# Schematic.net
KiCad netlist of a schematic drawn in EAGLE
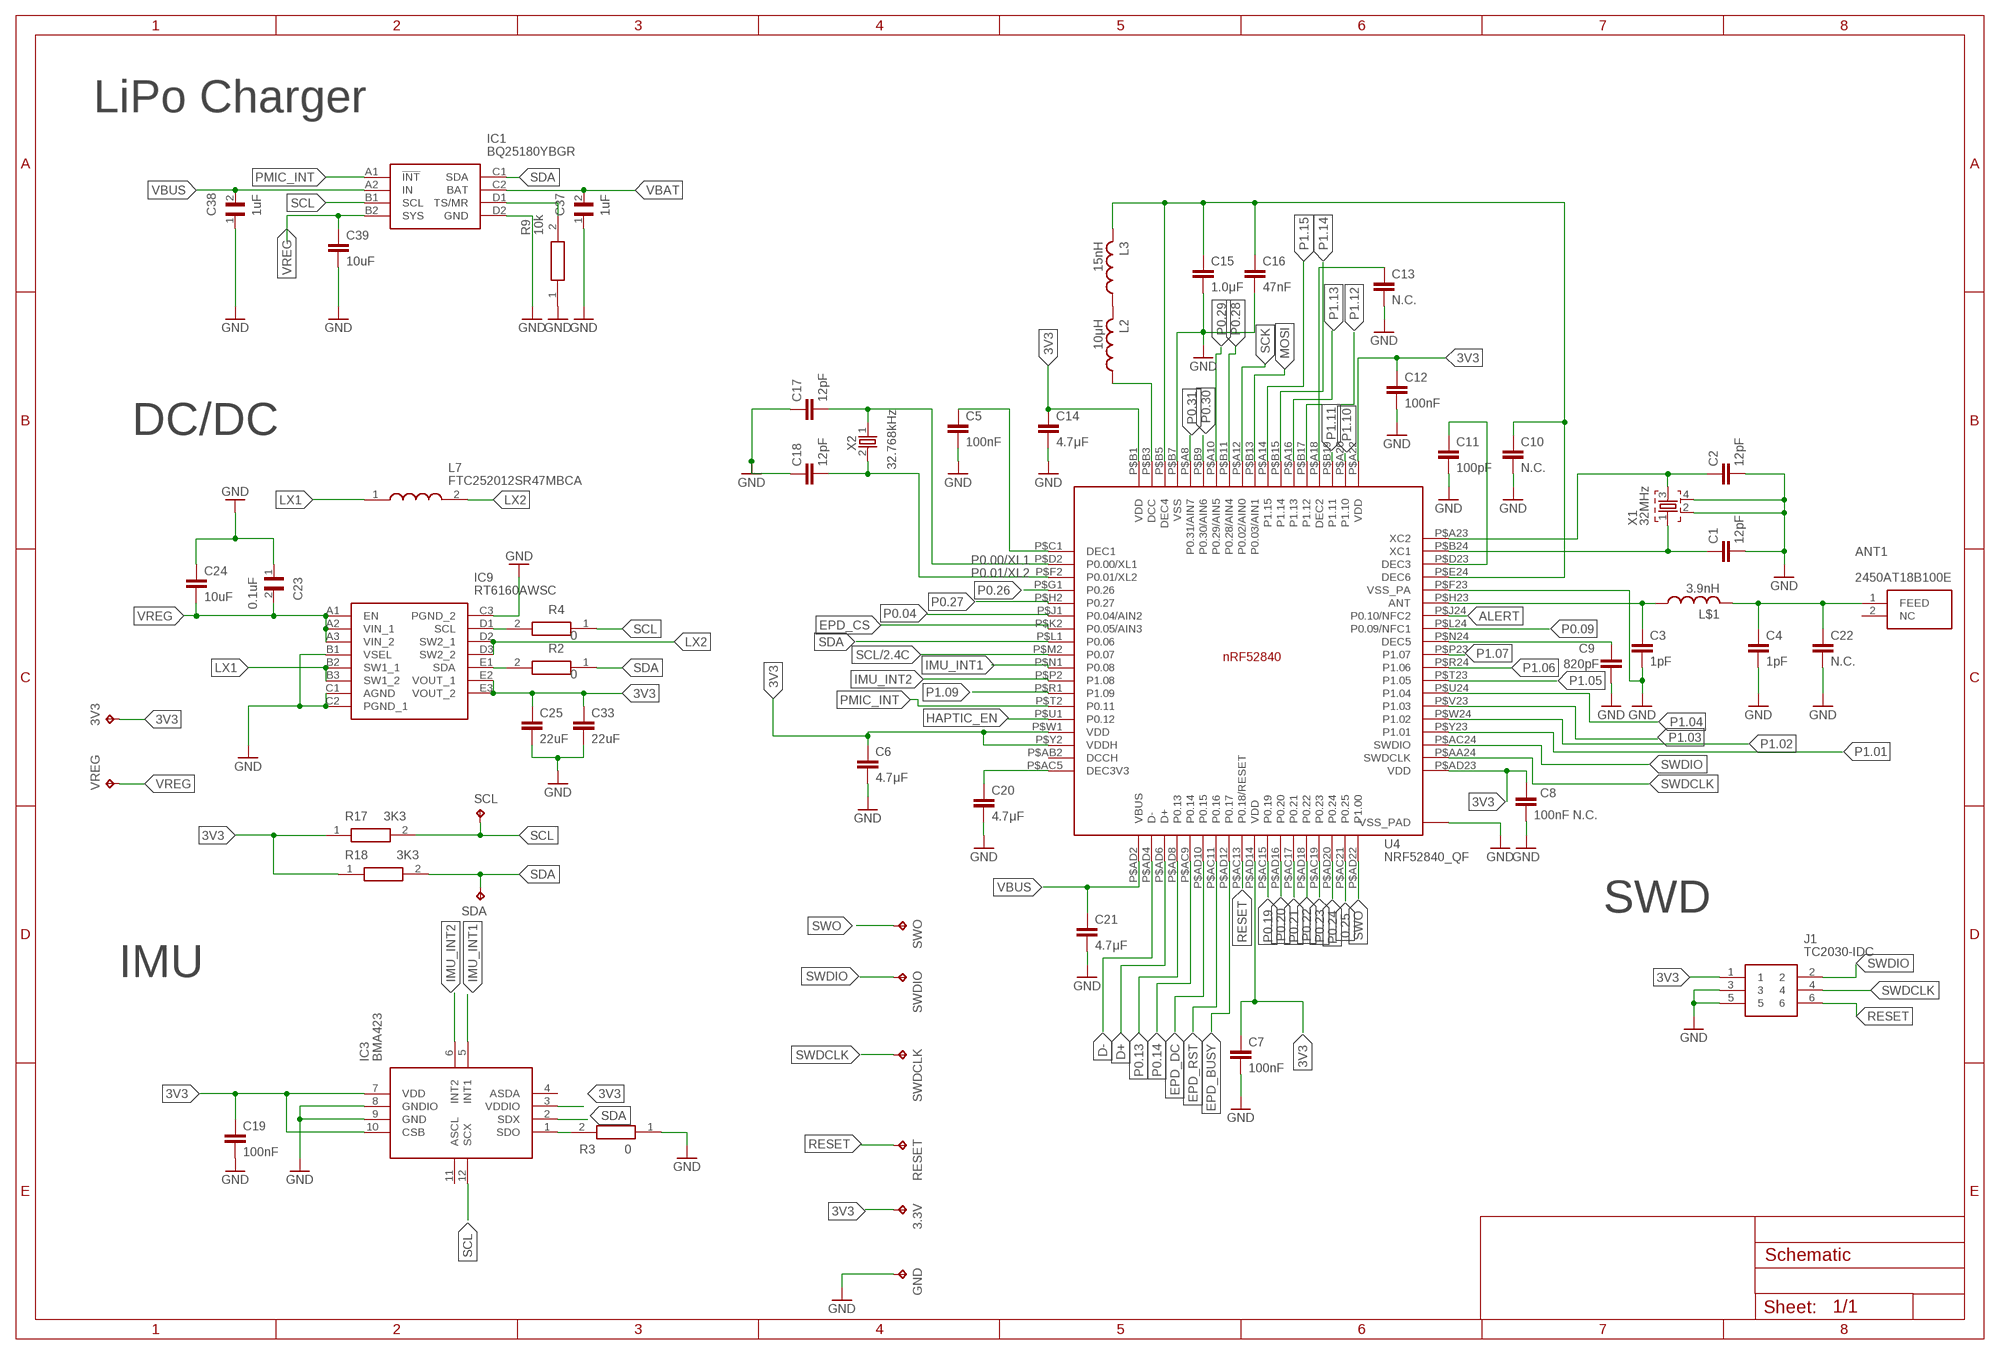
[diagram p0: schematic, sheet 1, part 1 of 2]
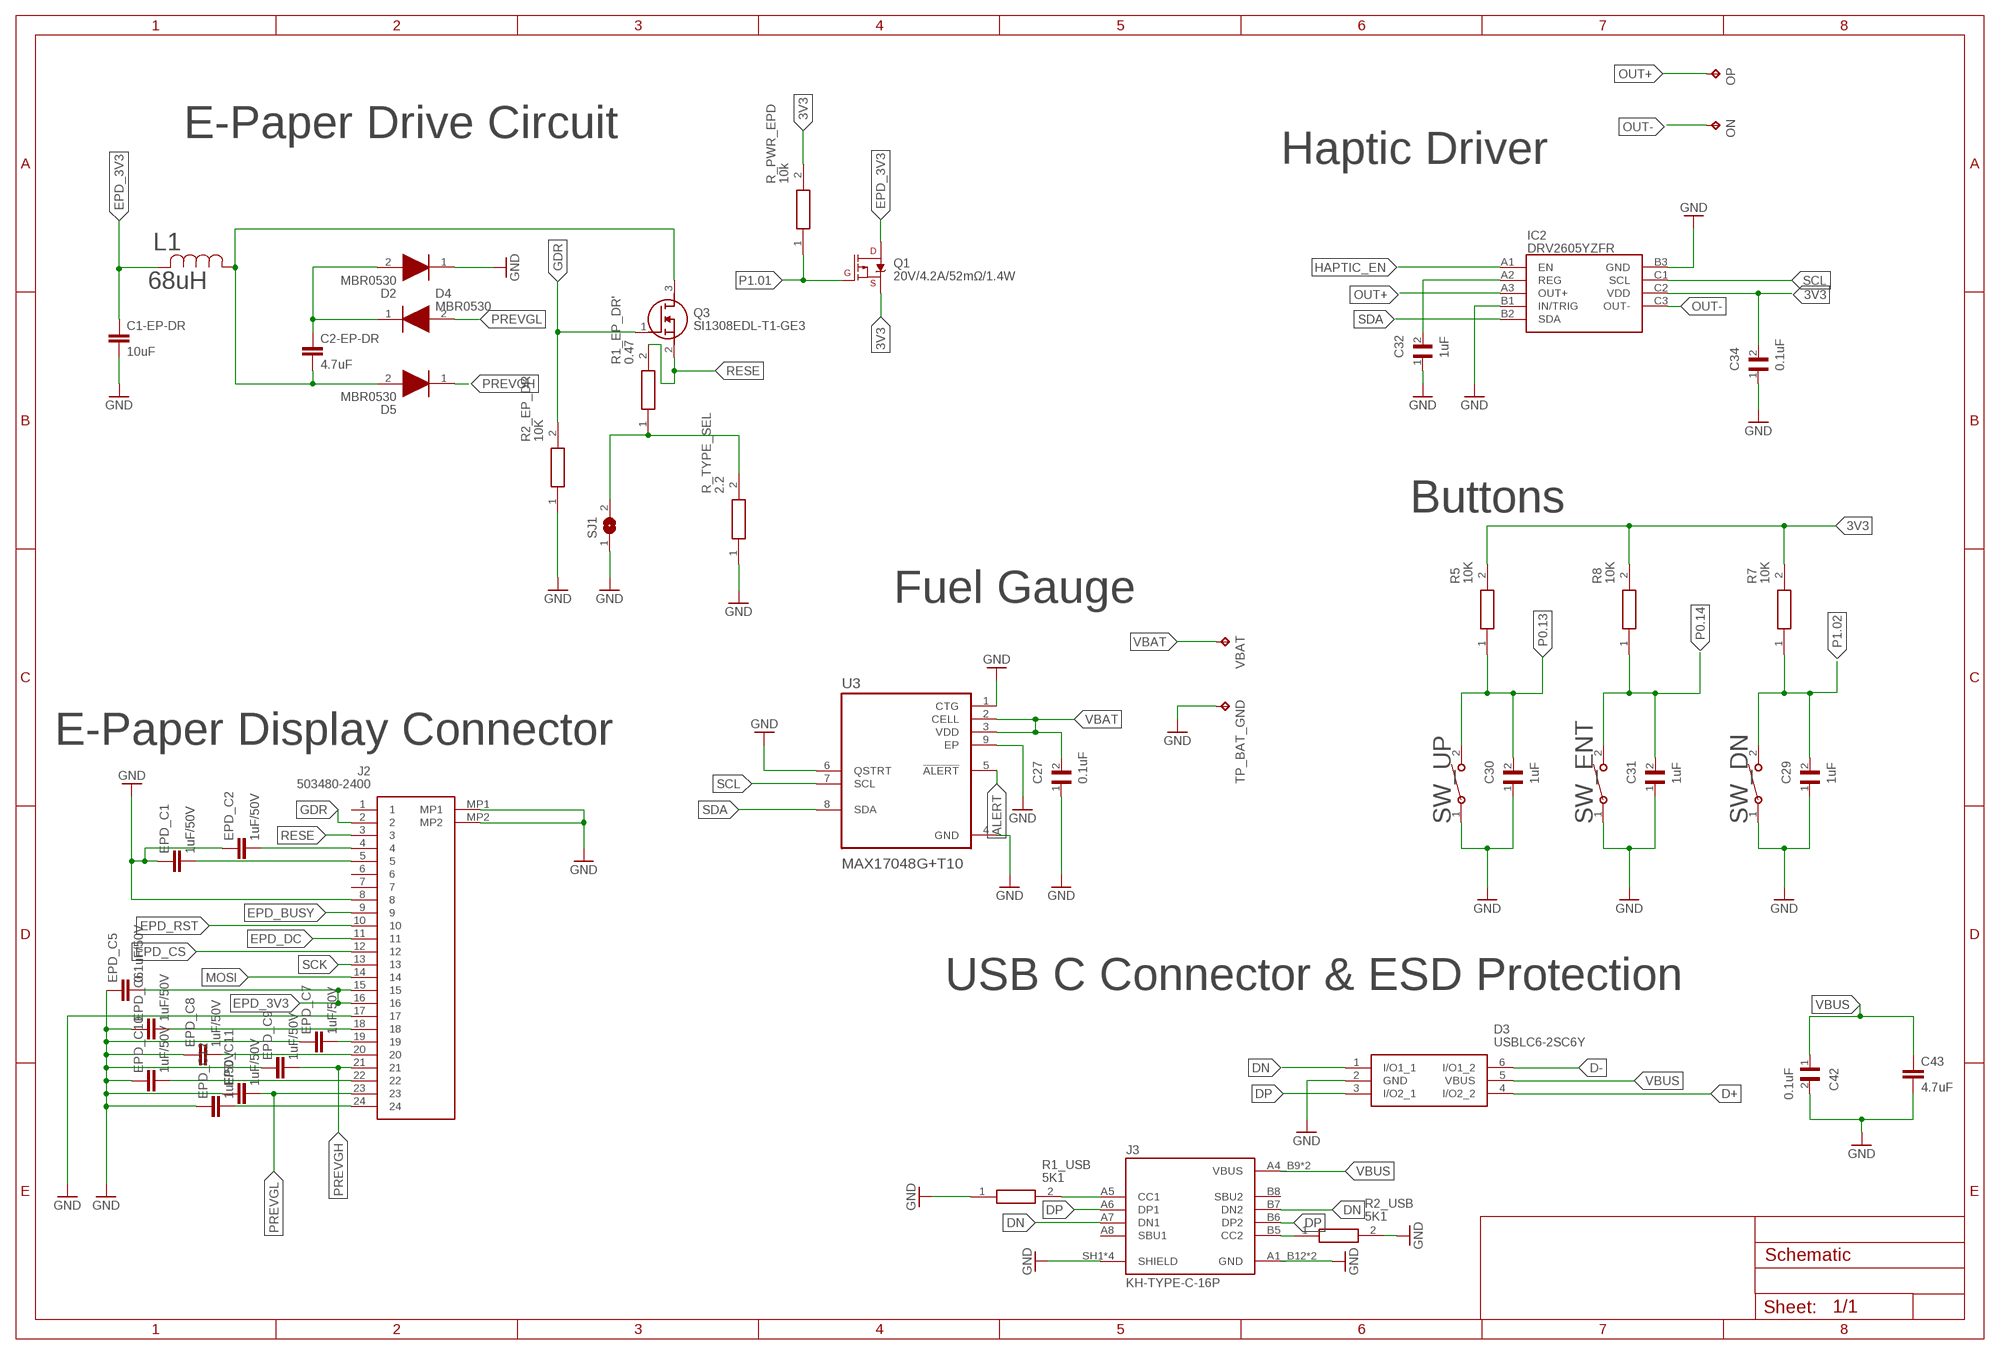
[diagram p1: schematic, sheet 1, part 2 of 2]

(export (version "E")
  (design (tool "Eeschema 10.0.6"))
  (components
    (comp (ref "3.3V")
      (value "HECTOR_WATCH_1_TPTP20R")
      (footprint "eagle-import:HECTOR_WATCH_1_TP20R")
      (libsource (lib "eagle-import") (part "HECTOR_WATCH_1_TPTP20R"))
    )
    (comp (ref "3V3")
      (value "HECTOR_WATCH_1_TPTP20R")
      (footprint "eagle-import:HECTOR_WATCH_1_TP20R")
      (libsource (lib "eagle-import") (part "HECTOR_WATCH_1_TPTP20R"))
    )
    (comp (ref "ANT1")
      (value "2450AT18B100E")
      (footprint "eagle-import:2450AT18B100E_ANTC3216X140N")
      (fields (field (name "MOUSER_PART_NUMBER") "609-2450AT18B100E"))
      (libsource (lib "eagle-import") (part "2450AT18B100E_2450AT18B100E"))
    )
    (comp (ref "C1")
      (value "12pF")
      (footprint "eagle-import:NORDIC_NRF_3_RESC0201_L")
      (libsource (lib "eagle-import") (part "NORDIC_NRF_3_CAPACITOR_0201_L"))
    )
    (comp (ref "C1-EP-DR")
      (value "10uF")
      (footprint "eagle-import:NORDIC_NRF_3_RESC0201_L")
      (libsource (lib "eagle-import") (part "NORDIC_NRF_3_CAPACITOR_0201_L"))
    )
    (comp (ref "C2")
      (value "12pF")
      (footprint "eagle-import:NORDIC_NRF_3_RESC0201_L")
      (libsource (lib "eagle-import") (part "NORDIC_NRF_3_CAPACITOR_0201_L"))
    )
    (comp (ref "C2-EP-DR")
      (value "4.7uF")
      (footprint "eagle-import:NORDIC_NRF_3_RESC0201_L")
      (libsource (lib "eagle-import") (part "NORDIC_NRF_3_CAPACITOR_0201_L"))
    )
    (comp (ref "C3")
      (value "1pF")
      (footprint "eagle-import:NORDIC_NRF_3_RESC0201_L")
      (libsource (lib "eagle-import") (part "NORDIC_NRF_3_CAPACITOR_0201_L"))
    )
    (comp (ref "C4")
      (value "1pF")
      (footprint "eagle-import:NORDIC_NRF_3_RESC0201_L")
      (libsource (lib "eagle-import") (part "NORDIC_NRF_3_CAPACITOR_0201_L"))
    )
    (comp (ref "C5")
      (value "100nF")
      (footprint "eagle-import:NORDIC_NRF_3_RESC0201_L")
      (libsource (lib "eagle-import") (part "NORDIC_NRF_3_CAPACITOR_0201_L"))
    )
    (comp (ref "C6")
      (value "4.7μF")
      (footprint "eagle-import:NORDIC_NRF_3_RESC0201_L")
      (libsource (lib "eagle-import") (part "NORDIC_NRF_3_CAPACITOR_0201_L"))
    )
    (comp (ref "C7")
      (value "100nF")
      (footprint "eagle-import:NORDIC_NRF_3_RESC0201_L")
      (libsource (lib "eagle-import") (part "NORDIC_NRF_3_CAPACITOR_0201_L"))
    )
    (comp (ref "C8")
      (value "100nF N.C.")
      (footprint "eagle-import:NORDIC_NRF_3_RESC0201_L")
      (libsource (lib "eagle-import") (part "NORDIC_NRF_3_CAPACITOR_0201_L"))
    )
    (comp (ref "C9")
      (value "820pF")
      (footprint "eagle-import:NORDIC_NRF_3_RESC0201_L")
      (libsource (lib "eagle-import") (part "NORDIC_NRF_3_CAPACITOR_0201_L"))
    )
    (comp (ref "C10")
      (value "N.C.")
      (footprint "eagle-import:NORDIC_NRF_3_RESC0201_L")
      (libsource (lib "eagle-import") (part "NORDIC_NRF_3_CAPACITOR_0201_L"))
    )
    (comp (ref "C11")
      (value "100pF")
      (footprint "eagle-import:NORDIC_NRF_3_RESC0201_L")
      (libsource (lib "eagle-import") (part "NORDIC_NRF_3_CAPACITOR_0201_L"))
    )
    (comp (ref "C12")
      (value "100nF")
      (footprint "eagle-import:NORDIC_NRF_3_RESC0201_L")
      (libsource (lib "eagle-import") (part "NORDIC_NRF_3_CAPACITOR_0201_L"))
    )
    (comp (ref "C13")
      (value "N.C.")
      (footprint "eagle-import:NORDIC_NRF_3_RESC0201_L")
      (libsource (lib "eagle-import") (part "NORDIC_NRF_3_CAPACITOR_0201_L"))
    )
    (comp (ref "C14")
      (value "4.7μF")
      (footprint "eagle-import:NORDIC_NRF_3_RESC0201_L")
      (libsource (lib "eagle-import") (part "NORDIC_NRF_3_CAPACITOR_0201_L"))
    )
    (comp (ref "C15")
      (value "1.0μF")
      (footprint "eagle-import:NORDIC_NRF_3_RESC0201_L")
      (libsource (lib "eagle-import") (part "NORDIC_NRF_3_CAPACITOR_0201_L"))
    )
    (comp (ref "C16")
      (value "47nF")
      (footprint "eagle-import:NORDIC_NRF_3_RESC0201_L")
      (libsource (lib "eagle-import") (part "NORDIC_NRF_3_CAPACITOR_0201_L"))
    )
    (comp (ref "C17")
      (value "12pF")
      (footprint "eagle-import:NORDIC_NRF_3_RESC0201_L")
      (libsource (lib "eagle-import") (part "NORDIC_NRF_3_CAPACITOR_0201_L"))
    )
    (comp (ref "C18")
      (value "12pF")
      (footprint "eagle-import:NORDIC_NRF_3_RESC0201_L")
      (libsource (lib "eagle-import") (part "NORDIC_NRF_3_CAPACITOR_0201_L"))
    )
    (comp (ref "C19")
      (value "100nF")
      (footprint "eagle-import:NORDIC_NRF_3_RESC0201_L")
      (libsource (lib "eagle-import") (part "NORDIC_NRF_3_CAPACITOR_0201_L"))
    )
    (comp (ref "C20")
      (value "4.7μF")
      (footprint "eagle-import:NORDIC_NRF_3_RESC0201_L")
      (libsource (lib "eagle-import") (part "NORDIC_NRF_3_CAPACITOR_0201_L"))
    )
    (comp (ref "C21")
      (value "4.7μF")
      (footprint "eagle-import:NORDIC_NRF_3_RESC0201_L")
      (libsource (lib "eagle-import") (part "NORDIC_NRF_3_CAPACITOR_0201_L"))
    )
    (comp (ref "C22")
      (value "N.C.")
      (footprint "eagle-import:NORDIC_NRF_3_RESC0201_L")
      (libsource (lib "eagle-import") (part "NORDIC_NRF_3_CAPACITOR_0201_L"))
    )
    (comp (ref "C23")
      (value "0.1uF")
      (footprint "eagle-import:GRM011R60J152KE01L_2_CAPC0201X13N")
      (fields (field (name "MF") "Murata") (field (name "MP") "GRM011R60J152KE01L"))
      (libsource (lib "eagle-import") (part "GRM011R60J152KE01L_2_GRM011R60J152KE01L"))
    )
    (comp (ref "C24")
      (value "10uF")
      (footprint "eagle-import:NORDIC_NRF_3_RESC0201_L")
      (libsource (lib "eagle-import") (part "NORDIC_NRF_3_CAPACITOR_0201_L"))
    )
    (comp (ref "C25")
      (value "22uF")
      (footprint "eagle-import:NORDIC_NRF_3_RESC0201_L")
      (libsource (lib "eagle-import") (part "NORDIC_NRF_3_CAPACITOR_0201_L"))
    )
    (comp (ref "C27")
      (value "0.1uF")
      (footprint "eagle-import:GRM011R60J152KE01L_2_CAPC0201X13N")
      (fields (field (name "MF") "Murata") (field (name "MP") "GRM011R60J152KE01L"))
      (libsource (lib "eagle-import") (part "GRM011R60J152KE01L_2_GRM011R60J152KE01L"))
    )
    (comp (ref "C29")
      (value "1uF")
      (footprint "eagle-import:GRM011R60J152KE01L_2_CAPC0201X13N")
      (fields (field (name "MF") "Murata") (field (name "MP") "GRM011R60J152KE01L"))
      (libsource (lib "eagle-import") (part "GRM011R60J152KE01L_2_GRM011R60J152KE01L"))
    )
    (comp (ref "C30")
      (value "1uF")
      (footprint "eagle-import:GRM011R60J152KE01L_2_CAPC0201X13N")
      (fields (field (name "MF") "Murata") (field (name "MP") "GRM011R60J152KE01L"))
      (libsource (lib "eagle-import") (part "GRM011R60J152KE01L_2_GRM011R60J152KE01L"))
    )
    (comp (ref "C31")
      (value "1uF")
      (footprint "eagle-import:GRM011R60J152KE01L_2_CAPC0201X13N")
      (fields (field (name "MF") "Murata") (field (name "MP") "GRM011R60J152KE01L"))
      (libsource (lib "eagle-import") (part "GRM011R60J152KE01L_2_GRM011R60J152KE01L"))
    )
    (comp (ref "C32")
      (value "1uF")
      (footprint "eagle-import:GRM011R60J152KE01L_2_CAPC0201X13N")
      (fields (field (name "MF") "Murata") (field (name "MP") "GRM011R60J152KE01L"))
      (libsource (lib "eagle-import") (part "GRM011R60J152KE01L_2_GRM011R60J152KE01L"))
    )
    (comp (ref "C33")
      (value "22uF")
      (footprint "eagle-import:NORDIC_NRF_3_RESC0201_L")
      (libsource (lib "eagle-import") (part "NORDIC_NRF_3_CAPACITOR_0201_L"))
    )
    (comp (ref "C34")
      (value "0.1uF")
      (footprint "eagle-import:GRM011R60J152KE01L_2_CAPC0201X13N")
      (fields (field (name "MF") "Murata") (field (name "MP") "GRM011R60J152KE01L"))
      (libsource (lib "eagle-import") (part "GRM011R60J152KE01L_2_GRM011R60J152KE01L"))
    )
    (comp (ref "C37")
      (value "1uF")
      (footprint "eagle-import:GRM011R60J152KE01L_2_CAPC0201X13N")
      (fields (field (name "MF") "Murata") (field (name "MP") "GRM011R60J152KE01L"))
      (libsource (lib "eagle-import") (part "GRM011R60J152KE01L_2_GRM011R60J152KE01L"))
    )
    (comp (ref "C38")
      (value "1uF")
      (footprint "eagle-import:GRM011R60J152KE01L_2_CAPC0201X13N")
      (fields (field (name "MF") "Murata") (field (name "MP") "GRM011R60J152KE01L"))
      (libsource (lib "eagle-import") (part "GRM011R60J152KE01L_2_GRM011R60J152KE01L"))
    )
    (comp (ref "C39")
      (value "10uF")
      (footprint "eagle-import:NORDIC_NRF_3_RESC0201_L")
      (libsource (lib "eagle-import") (part "NORDIC_NRF_3_CAPACITOR_0201_L"))
    )
    (comp (ref "C42")
      (value "0.1uF")
      (footprint "eagle-import:GRM011R60J152KE01L_2_CAPC0201X13N")
      (fields (field (name "MF") "Murata") (field (name "MP") "GRM011R60J152KE01L"))
      (libsource (lib "eagle-import") (part "GRM011R60J152KE01L_2_GRM011R60J152KE01L"))
    )
    (comp (ref "C43")
      (value "4.7uF")
      (footprint "eagle-import:NORDIC_NRF_3_RESC0201_L")
      (libsource (lib "eagle-import") (part "NORDIC_NRF_3_CAPACITOR_0201_L"))
    )
    (comp (ref "D2")
      (value "MBR0530")
      (footprint "eagle-import:ESP32_C6_LIBRARY_5_SOD3716X135N")
      (fields (field (name "MF") "ON Semiconductor"))
      (libsource (lib "eagle-import") (part "ESP32_C6_LIBRARY_5_MBR0530"))
    )
    (comp (ref "D3")
      (value "USBLC6-2SC6Y")
      (footprint "eagle-import:ESP32_C6_LIBRARY_3_SOT95P280X145-6N")
      (fields (field (name "MF") "STMicroelectronics"))
      (libsource (lib "eagle-import") (part "ESP32_C6_LIBRARY_3_USBLC6-2SC6Y"))
    )
    (comp (ref "D4")
      (value "MBR0530")
      (footprint "eagle-import:ESP32_C6_LIBRARY_5_SOD3716X135N")
      (fields (field (name "MF") "ON Semiconductor"))
      (libsource (lib "eagle-import") (part "ESP32_C6_LIBRARY_5_MBR0530"))
    )
    (comp (ref "D5")
      (value "MBR0530")
      (footprint "eagle-import:ESP32_C6_LIBRARY_5_SOD3716X135N")
      (fields (field (name "MF") "ON Semiconductor"))
      (libsource (lib "eagle-import") (part "ESP32_C6_LIBRARY_5_MBR0530"))
    )
    (comp (ref "EPD_C1")
      (value "1uF/50V")
      (footprint "eagle-import:NORDIC_NRF_3_RESC0201_L")
      (libsource (lib "eagle-import") (part "NORDIC_NRF_3_CAPACITOR_0201_L"))
    )
    (comp (ref "EPD_C2")
      (value "1uF/50V")
      (footprint "eagle-import:NORDIC_NRF_3_RESC0201_L")
      (libsource (lib "eagle-import") (part "NORDIC_NRF_3_CAPACITOR_0201_L"))
    )
    (comp (ref "EPD_C5")
      (value "0.1uF/50V")
      (footprint "eagle-import:NORDIC_NRF_3_RESC0201_L")
      (libsource (lib "eagle-import") (part "NORDIC_NRF_3_CAPACITOR_0201_L"))
    )
    (comp (ref "EPD_C6")
      (value "1uF/50V")
      (footprint "eagle-import:NORDIC_NRF_3_RESC0201_L")
      (libsource (lib "eagle-import") (part "NORDIC_NRF_3_CAPACITOR_0201_L"))
    )
    (comp (ref "EPD_C7")
      (value "1uF/50V")
      (footprint "eagle-import:NORDIC_NRF_3_RESC0201_L")
      (libsource (lib "eagle-import") (part "NORDIC_NRF_3_CAPACITOR_0201_L"))
    )
    (comp (ref "EPD_C8")
      (value "1uF/50V")
      (footprint "eagle-import:NORDIC_NRF_3_RESC0201_L")
      (libsource (lib "eagle-import") (part "NORDIC_NRF_3_CAPACITOR_0201_L"))
    )
    (comp (ref "EPD_C9")
      (value "1uF/50V")
      (footprint "eagle-import:NORDIC_NRF_3_RESC0201_L")
      (libsource (lib "eagle-import") (part "NORDIC_NRF_3_CAPACITOR_0201_L"))
    )
    (comp (ref "EPD_C10")
      (value "1uF/50V")
      (footprint "eagle-import:NORDIC_NRF_3_RESC0201_L")
      (libsource (lib "eagle-import") (part "NORDIC_NRF_3_CAPACITOR_0201_L"))
    )
    (comp (ref "EPD_C11")
      (value "1uF/50V")
      (footprint "eagle-import:NORDIC_NRF_3_RESC0201_L")
      (libsource (lib "eagle-import") (part "NORDIC_NRF_3_CAPACITOR_0201_L"))
    )
    (comp (ref "EPD_C12")
      (value "1uF/50V")
      (footprint "eagle-import:NORDIC_NRF_3_RESC0201_L")
      (libsource (lib "eagle-import") (part "NORDIC_NRF_3_CAPACITOR_0201_L"))
    )
    (comp (ref "GND")
      (value "HECTOR_WATCH_1_TPTP20R")
      (footprint "eagle-import:HECTOR_WATCH_1_TP20R")
      (libsource (lib "eagle-import") (part "HECTOR_WATCH_1_TPTP20R"))
    )
    (comp (ref "IC1")
      (value "BQ25180YBGR")
      (footprint "eagle-import:BQ25180YBGR_BGA8C40P2X4_100X155X50")
      (fields (field (name "MOUSER_PART_NUMBER") "595-BQ25180YBGR"))
      (libsource (lib "eagle-import") (part "BQ25180YBGR_BQ25180YBGR"))
    )
    (comp (ref "IC2")
      (value "DRV2605YZFR")
      (footprint "eagle-import:DRV2605YZFR_BGA9C50P3X3_144X144X62")
      (libsource (lib "eagle-import") (part "DRV2605YZFR_DRV2605YZFR"))
    )
    (comp (ref "IC3")
      (value "BMA423")
      (footprint "eagle-import:BMA423_BMA423")
      (fields (field (name "MOUSER_PART_NUMBER") "262-BMA423"))
      (libsource (lib "eagle-import") (part "BMA423_BMA423"))
    )
    (comp (ref "IC9")
      (value "RT6160AWSC")
      (footprint "eagle-import:RT6160AWSC_BGA15C40P3X5_140X230X60")
      (fields (field (name "MOUSER_PART_NUMBER") "835-RT6160AWSC"))
      (libsource (lib "eagle-import") (part "RT6160AWSC_RT6160AWSC"))
    )
    (comp (ref "J1")
      (value "TC2030-IDC")
      (footprint "eagle-import:TC2030-IDC_TC2030IDC")
      (libsource (lib "eagle-import") (part "TC2030-IDC_TC2030-IDC"))
    )
    (comp (ref "J2")
      (value "503480-2400")
      (footprint "eagle-import:503480-2400_5034802400")
      (fields (field (name "MOUSER_PART_NUMBER") "538-503480-2400"))
      (libsource (lib "eagle-import") (part "503480-2400_503480-2400"))
    )
    (comp (ref "J3")
      (value "KH-TYPE-C-16P")
      (footprint "eagle-import:KH-TYPE-C-16P_KINGHELM_KH-TYPE-C-16P")
      (fields (field (name "MF") "kinghelm"))
      (libsource (lib "eagle-import") (part "KH-TYPE-C-16P_KH-TYPE-C-16P"))
    )
    (comp (ref "L$1")
      (value "3.9nH")
      (footprint "eagle-import:NORDIC_NRF_2_RESC0402_L")
      (libsource (lib "eagle-import") (part "NORDIC_NRF_2_INDUCTOR_0402_L"))
    )
    (comp (ref "L1")
      (value "68uH")
      (footprint "eagle-import:ESP32_C6_LIBRARY_2_IND_4828-WE-TPC_WRE")
      (fields
        (field (name "MANUFACTURER_PART_NUMBER") "744043680")
        (field (name "COPYRIGHT") "Copyright (C) 2024 Ultra Librarian. All rights reserved.")
      )
      (libsource (lib "eagle-import") (part "ESP32_C6_LIBRARY_2_744043680IND_4828-WE-TPC_WRE"))
    )
    (comp (ref "L2")
      (value "10μH")
      (footprint "eagle-import:NORDIC_NRF_2_RESC0201_L")
      (libsource (lib "eagle-import") (part "NORDIC_NRF_2_INDUCTOR_0201_L"))
    )
    (comp (ref "L3")
      (value "15nH")
      (footprint "eagle-import:NORDIC_NRF_2_RESC0201_L")
      (libsource (lib "eagle-import") (part "NORDIC_NRF_2_INDUCTOR_0201_L"))
    )
    (comp (ref "L7")
      (value "FTC252012SR47MBCA")
      (footprint "eagle-import:MLP2016SR47MT0S1_INDC2016X100N")
      (libsource (lib "eagle-import") (part "MLP2016SR47MT0S1_FTC252012SR47MBCA"))
    )
    (comp (ref "ON")
      (value "HECTOR_WATCH_1_TPTP20R")
      (footprint "eagle-import:HECTOR_WATCH_1_TP20R")
      (libsource (lib "eagle-import") (part "HECTOR_WATCH_1_TPTP20R"))
    )
    (comp (ref "OP")
      (value "HECTOR_WATCH_1_TPTP20R")
      (footprint "eagle-import:HECTOR_WATCH_1_TP20R")
      (libsource (lib "eagle-import") (part "HECTOR_WATCH_1_TPTP20R"))
    )
    (comp (ref "Q1")
      (value "20V/4.2A/52mΩ/1.4W")
      (footprint "eagle-import:ESP32_C6_LIBRARY_4_ESP32_C6_LIBRARY_4_ESP32_C6_LIBRARY_4_ESP32_C6_LIBRARY_4_ESP32_WROVER_SPARKFUN-DISCRETESEMI_SOT23-3")
      (libsource (lib "eagle-import") (part "ESP32_C6_LIBRARY_4_ESP32_WROVER_SPARKFUN-DISCRETESEMI_MOSFET_PCH-DMG2305UX-7"))
    )
    (comp (ref "Q3")
      (value "SI1308EDL-T1-GE3")
      (footprint "eagle-import:ESP32_C6_LIBRARY_6_SOT65P210X110-3N")
      (fields (field (name "MF") "Vishay Siliconix"))
      (libsource (lib "eagle-import") (part "ESP32_C6_LIBRARY_6_SI1308EDL-T1-GE3"))
    )
    (comp (ref "R1_EP_DR'")
      (value "0.47")
      (footprint "eagle-import:ERA-1AEB3401C_0201")
      (libsource (lib "eagle-import") (part "ERA-1AEB3401C_CPF0201D7K68C1"))
    )
    (comp (ref "R1_USB")
      (value "5K1")
      (footprint "eagle-import:ERA-1AEB3401C_0201")
      (libsource (lib "eagle-import") (part "ERA-1AEB3401C_CPF0201D7K68C1"))
    )
    (comp (ref "R2")
      (value "0")
      (footprint "eagle-import:ERA-1AEB3401C_0201")
      (libsource (lib "eagle-import") (part "ERA-1AEB3401C_CPF0201D7K68C1"))
    )
    (comp (ref "R2_EP_DR")
      (value "10K")
      (footprint "eagle-import:ERA-1AEB3401C_0201")
      (libsource (lib "eagle-import") (part "ERA-1AEB3401C_CPF0201D7K68C1"))
    )
    (comp (ref "R2_USB")
      (value "5K1")
      (footprint "eagle-import:ERA-1AEB3401C_0201")
      (libsource (lib "eagle-import") (part "ERA-1AEB3401C_CPF0201D7K68C1"))
    )
    (comp (ref "R3")
      (value "0")
      (footprint "eagle-import:ERA-1AEB3401C_0201")
      (libsource (lib "eagle-import") (part "ERA-1AEB3401C_CPF0201D7K68C1"))
    )
    (comp (ref "R4")
      (value "0")
      (footprint "eagle-import:ERA-1AEB3401C_0201")
      (libsource (lib "eagle-import") (part "ERA-1AEB3401C_CPF0201D7K68C1"))
    )
    (comp (ref "R5")
      (value "10K")
      (footprint "eagle-import:ERA-1AEB3401C_0201")
      (libsource (lib "eagle-import") (part "ERA-1AEB3401C_CPF0201D7K68C1"))
    )
    (comp (ref "R7")
      (value "10K")
      (footprint "eagle-import:ERA-1AEB3401C_0201")
      (libsource (lib "eagle-import") (part "ERA-1AEB3401C_CPF0201D7K68C1"))
    )
    (comp (ref "R8")
      (value "10K")
      (footprint "eagle-import:ERA-1AEB3401C_0201")
      (libsource (lib "eagle-import") (part "ERA-1AEB3401C_CPF0201D7K68C1"))
    )
    (comp (ref "R9")
      (value "10k")
      (footprint "eagle-import:CPF0201D7K68C1_0201")
      (libsource (lib "eagle-import") (part "CPF0201D7K68C1_CPF0201D7K68C1"))
    )
    (comp (ref "R17")
      (value "3K3")
      (footprint "eagle-import:ERA-1AEB3401C_0201")
      (libsource (lib "eagle-import") (part "ERA-1AEB3401C_CPF0201D7K68C1"))
    )
    (comp (ref "R18")
      (value "3K3")
      (footprint "eagle-import:ERA-1AEB3401C_0201")
      (libsource (lib "eagle-import") (part "ERA-1AEB3401C_CPF0201D7K68C1"))
    )
    (comp (ref "RESET")
      (value "HECTOR_WATCH_1_TPTP20R")
      (footprint "eagle-import:HECTOR_WATCH_1_TP20R")
      (libsource (lib "eagle-import") (part "HECTOR_WATCH_1_TPTP20R"))
    )
    (comp (ref "R_PWR_EPD")
      (value "10k")
      (footprint "eagle-import:ERA-1AEB3401C_0201")
      (libsource (lib "eagle-import") (part "ERA-1AEB3401C_CPF0201D7K68C1"))
    )
    (comp (ref "R_TYPE_SEL")
      (value "2.2")
      (footprint "eagle-import:ERA-1AEB3401C_0201")
      (libsource (lib "eagle-import") (part "ERA-1AEB3401C_CPF0201D7K68C1"))
    )
    (comp (ref "SCL")
      (value "HECTOR_WATCH_1_TPTP20R")
      (footprint "eagle-import:HECTOR_WATCH_1_TP20R")
      (libsource (lib "eagle-import") (part "HECTOR_WATCH_1_TPTP20R"))
    )
    (comp (ref "SDA")
      (value "HECTOR_WATCH_1_TPTP20R")
      (footprint "eagle-import:HECTOR_WATCH_1_TP20R")
      (libsource (lib "eagle-import") (part "HECTOR_WATCH_1_TPTP20R"))
    )
    (comp (ref "SJ1")
      (value "ESP32_C6_LIBRARY_7_JUMPER_SJ")
      (footprint "eagle-import:ESP32_C6_LIBRARY_7_JUMPER_SJ")
      (libsource (lib "eagle-import") (part "ESP32_C6_LIBRARY_7_JUMPER_SJ"))
    )
    (comp (ref "SWDCLK")
      (value "HECTOR_WATCH_1_TPTP20R")
      (footprint "eagle-import:HECTOR_WATCH_1_TP20R")
      (libsource (lib "eagle-import") (part "HECTOR_WATCH_1_TPTP20R"))
    )
    (comp (ref "SWDIO")
      (value "HECTOR_WATCH_1_TPTP20R")
      (footprint "eagle-import:HECTOR_WATCH_1_TP20R")
      (libsource (lib "eagle-import") (part "HECTOR_WATCH_1_TPTP20R"))
    )
    (comp (ref "SWO")
      (value "HECTOR_WATCH_1_TPTP20R")
      (footprint "eagle-import:HECTOR_WATCH_1_TP20R")
      (libsource (lib "eagle-import") (part "HECTOR_WATCH_1_TPTP20R"))
    )
    (comp (ref "SW_DN")
      (value "2025-10-22_07-23-44_LIBRARY_EVP-AKE31ASW_EVP-AKE31A_PAN")
      (footprint "eagle-import:2025-10-22_07-23-44_LIBRARY_SW_EVP-AKE31A_PAN")
      (fields
        (field (name "MANUFACTURER_PART_NUMBER") "EVP-AKE31A")
        (field (name "COPYRIGHT") "Copyright (C) 2025 Ultra Librarian. All rights reserved.")
      )
      (libsource (lib "eagle-import") (part "2025-10-22_07-23-44_LIBRARY_EVP-AKE31ASW_EVP-AKE31A_PAN"))
    )
    (comp (ref "SW_ENT")
      (value "2025-10-22_07-23-44_LIBRARY_EVP-AKE31ASW_EVP-AKE31A_PAN")
      (footprint "eagle-import:2025-10-22_07-23-44_LIBRARY_SW_EVP-AKE31A_PAN")
      (fields
        (field (name "MANUFACTURER_PART_NUMBER") "EVP-AKE31A")
        (field (name "COPYRIGHT") "Copyright (C) 2025 Ultra Librarian. All rights reserved.")
      )
      (libsource (lib "eagle-import") (part "2025-10-22_07-23-44_LIBRARY_EVP-AKE31ASW_EVP-AKE31A_PAN"))
    )
    (comp (ref "SW_UP")
      (value "2025-10-22_07-23-44_LIBRARY_EVP-AKE31ASW_EVP-AKE31A_PAN")
      (footprint "eagle-import:2025-10-22_07-23-44_LIBRARY_SW_EVP-AKE31A_PAN")
      (fields
        (field (name "MANUFACTURER_PART_NUMBER") "EVP-AKE31A")
        (field (name "COPYRIGHT") "Copyright (C) 2025 Ultra Librarian. All rights reserved.")
      )
      (libsource (lib "eagle-import") (part "2025-10-22_07-23-44_LIBRARY_EVP-AKE31ASW_EVP-AKE31A_PAN"))
    )
    (comp (ref "TP_BAT_GND")
      (value "HECTOR_WATCH_1_TPTP20R")
      (footprint "eagle-import:HECTOR_WATCH_1_TP20R")
      (libsource (lib "eagle-import") (part "HECTOR_WATCH_1_TPTP20R"))
    )
    (comp (ref "U3")
      (value "MAX17048G+T10")
      (footprint "eagle-import:ESP32_C6_LIBRARY_SON50P200X200X80-9N")
      (fields (field (name "MF") "Analog Devices"))
      (libsource (lib "eagle-import") (part "ESP32_C6_LIBRARY_MAX17048G+T10"))
    )
    (comp (ref "U4")
      (value "NRF52840_QF")
      (footprint "eagle-import:NORDIC_NRF_4_AQFN50P700X700X85_HS-74N")
      (libsource (lib "eagle-import") (part "NORDIC_NRF_4_NRF52840_QF"))
    )
    (comp (ref "VBAT")
      (value "HECTOR_WATCH_1_TPTP20R")
      (footprint "eagle-import:HECTOR_WATCH_1_TP20R")
      (libsource (lib "eagle-import") (part "HECTOR_WATCH_1_TPTP20R"))
    )
    (comp (ref "VREG")
      (value "HECTOR_WATCH_1_TPTP20R")
      (footprint "eagle-import:HECTOR_WATCH_1_TP20R")
      (libsource (lib "eagle-import") (part "HECTOR_WATCH_1_TPTP20R"))
    )
    (comp (ref "X1")
      (value "32MHz")
      (footprint "eagle-import:NORDIC_NRF_BT-XTAL_2016_N")
      (libsource (lib "eagle-import") (part "NORDIC_NRF_XTAL_32MHZ"))
    )
    (comp (ref "X2")
      (value "32.768kHz")
      (footprint "eagle-import:NORDIC_NRF_1_XTAL_3215_N")
      (libsource (lib "eagle-import") (part "NORDIC_NRF_1_XTAL_32KHZ"))
    )
  )
  (nets
    (net (code "1") (name "/P0.00{slash}XL1") (class "Default")
      (node (ref "C17") (pin "2") (pinfunction "2_2") (pintype "passive"))
      (node (ref "U4") (pin "P$D2") (pinfunction "P0.00/XL1_P$D2") (pintype "bidirectional"))
      (node (ref "X2") (pin "1") (pinfunction "1_1") (pintype "passive"))
    )
    (net (code "2") (name "/P0.01{slash}XL2") (class "Default")
      (node (ref "C18") (pin "2") (pinfunction "2_2") (pintype "passive"))
      (node (ref "U4") (pin "P$F2") (pinfunction "P0.01/XL2_P$F2") (pintype "bidirectional"))
      (node (ref "X2") (pin "2") (pinfunction "2_2") (pintype "passive"))
    )
    (net (code "3") (name "0.25") (class "Default")
      (node (ref "U4") (pin "P$AC21") (pinfunction "P0.25_P$AC21") (pintype "bidirectional"))
    )
    (net (code "4") (name "3V3") (class "Default")
      (node (ref "3.3V") (pin "TP") (pinfunction "TP_TP") (pintype "input"))
      (node (ref "3V3") (pin "TP") (pinfunction "TP_TP") (pintype "input"))
      (node (ref "C12") (pin "1") (pinfunction "1_1") (pintype "passive"))
      (node (ref "C14") (pin "1") (pinfunction "1_1") (pintype "passive"))
      (node (ref "C19") (pin "1") (pinfunction "1_1") (pintype "passive"))
      (node (ref "C25") (pin "1") (pinfunction "1_1") (pintype "passive"))
      (node (ref "C33") (pin "1") (pinfunction "1_1") (pintype "passive"))
      (node (ref "C34") (pin "2") (pinfunction "2_2") (pintype "passive"))
      (node (ref "C6") (pin "1") (pinfunction "1_1") (pintype "passive"))
      (node (ref "C7") (pin "1") (pinfunction "1_1") (pintype "passive"))
      (node (ref "C8") (pin "1") (pinfunction "1_1") (pintype "passive"))
      (node (ref "IC2") (pin "C2") (pinfunction "VDD_C2") (pintype "bidirectional"))
      (node (ref "IC3") (pin "10") (pinfunction "CSB_10") (pintype "bidirectional"))
      (node (ref "IC3") (pin "3") (pinfunction "VDDIO_3") (pintype "bidirectional"))
      (node (ref "IC3") (pin "7") (pinfunction "VDD_7") (pintype "bidirectional"))
      (node (ref "IC9") (pin "E2") (pinfunction "VOUT_1_E2") (pintype "bidirectional"))
      (node (ref "IC9") (pin "E3") (pinfunction "VOUT_2_E3") (pintype "bidirectional"))
      (node (ref "J1") (pin "1") (pinfunction "1_1") (pintype "bidirectional"))
      (node (ref "Q1") (pin "2") (pinfunction "S_2") (pintype "bidirectional"))
      (node (ref "R17") (pin "1") (pinfunction "1_1") (pintype "bidirectional"))
      (node (ref "R18") (pin "1") (pinfunction "1_1") (pintype "bidirectional"))
      (node (ref "R5") (pin "2") (pinfunction "2_2") (pintype "bidirectional"))
      (node (ref "R7") (pin "2") (pinfunction "2_2") (pintype "bidirectional"))
      (node (ref "R8") (pin "2") (pinfunction "2_2") (pintype "bidirectional"))
      (node (ref "R_PWR_EPD") (pin "2") (pinfunction "2_2") (pintype "bidirectional"))
      (node (ref "U4") (pin "P$A22") (pinfunction "VDD_P$A22") (pintype "power_in"))
      (node (ref "U4") (pin "P$AD14") (pinfunction "VDD_P$AD14") (pintype "power_in"))
      (node (ref "U4") (pin "P$AD23") (pinfunction "VDD_P$AD23") (pintype "power_in"))
      (node (ref "U4") (pin "P$B1") (pinfunction "VDD_P$B1") (pintype "power_in"))
      (node (ref "U4") (pin "P$W1") (pinfunction "VDD_P$W1") (pintype "power_in"))
      (node (ref "U4") (pin "P$Y2") (pinfunction "VDDH_P$Y2") (pintype "power_in"))
    )
    (net (code "5") (name "ALERT") (class "Default")
      (node (ref "U3") (pin "5") (pinfunction "~{ALERT}_5") (pintype "output"))
      (node (ref "U4") (pin "P$J24") (pinfunction "P0.10/NFC2_P$J24") (pintype "bidirectional"))
    )
    (net (code "6") (name "D+") (class "Default")
      (node (ref "D3") (pin "4") (pinfunction "I/O2_2_4") (pintype "bidirectional"))
      (node (ref "U4") (pin "P$AD6") (pinfunction "D+_P$AD6") (pintype "bidirectional"))
    )
    (net (code "7") (name "D-") (class "Default")
      (node (ref "D3") (pin "6") (pinfunction "I/O1_2_6") (pintype "bidirectional"))
      (node (ref "U4") (pin "P$AD4") (pinfunction "D-_P$AD4") (pintype "bidirectional"))
    )
    (net (code "8") (name "DN") (class "Default")
      (node (ref "D3") (pin "1") (pinfunction "I/O1_1_1") (pintype "bidirectional"))
      (node (ref "J3") (pin "A7") (pinfunction "DN1_A7") (pintype "bidirectional"))
      (node (ref "J3") (pin "B7") (pinfunction "DN2_B7") (pintype "bidirectional"))
    )
    (net (code "9") (name "DP") (class "Default")
      (node (ref "D3") (pin "3") (pinfunction "I/O2_1_3") (pintype "bidirectional"))
      (node (ref "J3") (pin "A6") (pinfunction "DP1_A6") (pintype "bidirectional"))
      (node (ref "J3") (pin "B6") (pinfunction "DP2_B6") (pintype "bidirectional"))
    )
    (net (code "10") (name "EPD_3V3") (class "Default")
      (node (ref "C1-EP-DR") (pin "1") (pinfunction "1_1") (pintype "passive"))
      (node (ref "EPD_C5") (pin "2") (pinfunction "2_2") (pintype "passive"))
      (node (ref "J2") (pin "15") (pinfunction "15_15") (pintype "bidirectional"))
      (node (ref "J2") (pin "16") (pinfunction "16_16") (pintype "bidirectional"))
      (node (ref "L1") (pin "2") (pinfunction "2_2") (pintype "passive"))
      (node (ref "Q1") (pin "3") (pinfunction "D_3") (pintype "bidirectional"))
    )
    (net (code "11") (name "EPD_BUSY") (class "Default")
      (node (ref "J2") (pin "9") (pinfunction "9_9") (pintype "bidirectional"))
      (node (ref "U4") (pin "P$AD12") (pinfunction "P0.17_P$AD12") (pintype "bidirectional"))
    )
    (net (code "12") (name "EPD_CS") (class "Default")
      (node (ref "J2") (pin "12") (pinfunction "12_12") (pintype "bidirectional"))
      (node (ref "U4") (pin "P$K2") (pinfunction "P0.05/AIN3_P$K2") (pintype "bidirectional"))
    )
    (net (code "13") (name "EPD_DC") (class "Default")
      (node (ref "J2") (pin "11") (pinfunction "11_11") (pintype "bidirectional"))
      (node (ref "U4") (pin "P$AD10") (pinfunction "P0.15_P$AD10") (pintype "bidirectional"))
    )
    (net (code "14") (name "EPD_RST") (class "Default")
      (node (ref "J2") (pin "10") (pinfunction "10_10") (pintype "bidirectional"))
      (node (ref "U4") (pin "P$AC11") (pinfunction "P0.16_P$AC11") (pintype "bidirectional"))
    )
    (net (code "15") (name "GDR") (class "Default")
      (node (ref "J2") (pin "2") (pinfunction "2_2") (pintype "bidirectional"))
      (node (ref "Q3") (pin "1") (pinfunction "G_1") (pintype "bidirectional"))
      (node (ref "R2_EP_DR") (pin "2") (pinfunction "2_2") (pintype "bidirectional"))
    )
    (net (code "16") (name "GND") (class "Default")
      (node (ref "C1") (pin "2") (pinfunction "2_2") (pintype "passive"))
      (node (ref "C1-EP-DR") (pin "2") (pinfunction "2_2") (pintype "passive"))
      (node (ref "C10") (pin "2") (pinfunction "2_2") (pintype "passive"))
      (node (ref "C11") (pin "2") (pinfunction "2_2") (pintype "passive"))
      (node (ref "C12") (pin "2") (pinfunction "2_2") (pintype "passive"))
      (node (ref "C13") (pin "2") (pinfunction "2_2") (pintype "passive"))
      (node (ref "C14") (pin "2") (pinfunction "2_2") (pintype "passive"))
      (node (ref "C15") (pin "2") (pinfunction "2_2") (pintype "passive"))
      (node (ref "C16") (pin "2") (pinfunction "2_2") (pintype "passive"))
      (node (ref "C17") (pin "1") (pinfunction "1_1") (pintype "passive"))
      (node (ref "C18") (pin "1") (pinfunction "1_1") (pintype "passive"))
      (node (ref "C19") (pin "2") (pinfunction "2_2") (pintype "passive"))
      (node (ref "C2") (pin "2") (pinfunction "2_2") (pintype "passive"))
      (node (ref "C20") (pin "2") (pinfunction "2_2") (pintype "passive"))
      (node (ref "C21") (pin "2") (pinfunction "2_2") (pintype "passive"))
      (node (ref "C22") (pin "2") (pinfunction "2_2") (pintype "passive"))
      (node (ref "C23") (pin "1") (pinfunction "1_1") (pintype "passive"))
      (node (ref "C24") (pin "1") (pinfunction "1_1") (pintype "passive"))
      (node (ref "C25") (pin "2") (pinfunction "2_2") (pintype "passive"))
      (node (ref "C27") (pin "1") (pinfunction "1_1") (pintype "passive"))
      (node (ref "C29") (pin "1") (pinfunction "1_1") (pintype "passive"))
      (node (ref "C3") (pin "2") (pinfunction "2_2") (pintype "passive"))
      (node (ref "C30") (pin "1") (pinfunction "1_1") (pintype "passive"))
      (node (ref "C31") (pin "1") (pinfunction "1_1") (pintype "passive"))
      (node (ref "C32") (pin "1") (pinfunction "1_1") (pintype "passive"))
      (node (ref "C33") (pin "2") (pinfunction "2_2") (pintype "passive"))
      (node (ref "C34") (pin "1") (pinfunction "1_1") (pintype "passive"))
      (node (ref "C37") (pin "1") (pinfunction "1_1") (pintype "passive"))
      (node (ref "C38") (pin "1") (pinfunction "1_1") (pintype "passive"))
      (node (ref "C39") (pin "2") (pinfunction "2_2") (pintype "passive"))
      (node (ref "C4") (pin "2") (pinfunction "2_2") (pintype "passive"))
      (node (ref "C42") (pin "2") (pinfunction "2_2") (pintype "passive"))
      (node (ref "C43") (pin "2") (pinfunction "2_2") (pintype "passive"))
      (node (ref "C5") (pin "2") (pinfunction "2_2") (pintype "passive"))
      (node (ref "C6") (pin "2") (pinfunction "2_2") (pintype "passive"))
      (node (ref "C7") (pin "2") (pinfunction "2_2") (pintype "passive"))
      (node (ref "C8") (pin "2") (pinfunction "2_2") (pintype "passive"))
      (node (ref "C9") (pin "2") (pinfunction "2_2") (pintype "passive"))
      (node (ref "D2") (pin "1") (pinfunction "K_1") (pintype "bidirectional"))
      (node (ref "D3") (pin "2") (pinfunction "GND_2") (pintype "bidirectional"))
      (node (ref "EPD_C1") (pin "1") (pinfunction "1_1") (pintype "passive"))
      (node (ref "EPD_C10") (pin "1") (pinfunction "1_1") (pintype "passive"))
      (node (ref "EPD_C11") (pin "1") (pinfunction "1_1") (pintype "passive"))
      (node (ref "EPD_C12") (pin "1") (pinfunction "1_1") (pintype "passive"))
      (node (ref "EPD_C2") (pin "1") (pinfunction "1_1") (pintype "passive"))
      (node (ref "EPD_C5") (pin "1") (pinfunction "1_1") (pintype "passive"))
      (node (ref "EPD_C6") (pin "1") (pinfunction "1_1") (pintype "passive"))
      (node (ref "EPD_C7") (pin "1") (pinfunction "1_1") (pintype "passive"))
      (node (ref "EPD_C8") (pin "1") (pinfunction "1_1") (pintype "passive"))
      (node (ref "EPD_C9") (pin "1") (pinfunction "1_1") (pintype "passive"))
      (node (ref "GND") (pin "TP") (pinfunction "TP_TP") (pintype "input"))
      (node (ref "IC1") (pin "D2") (pinfunction "GND_D2") (pintype "bidirectional"))
      (node (ref "IC2") (pin "B1") (pinfunction "IN/TRIG_B1") (pintype "bidirectional"))
      (node (ref "IC2") (pin "B3") (pinfunction "GND_B3") (pintype "bidirectional"))
      (node (ref "IC3") (pin "8") (pinfunction "GNDIO_8") (pintype "bidirectional"))
      (node (ref "IC3") (pin "9") (pinfunction "GND_9") (pintype "bidirectional"))
      (node (ref "IC9") (pin "B1") (pinfunction "VSEL_B1") (pintype "bidirectional"))
      (node (ref "IC9") (pin "C1") (pinfunction "AGND_C1") (pintype "bidirectional"))
      (node (ref "IC9") (pin "C2") (pinfunction "PGND_1_C2") (pintype "bidirectional"))
      (node (ref "IC9") (pin "C3") (pinfunction "PGND_2_C3") (pintype "bidirectional"))
      (node (ref "J1") (pin "3") (pinfunction "3_3") (pintype "bidirectional"))
      (node (ref "J1") (pin "5") (pinfunction "5_5") (pintype "bidirectional"))
      (node (ref "J2") (pin "17") (pinfunction "17_17") (pintype "bidirectional"))
      (node (ref "J2") (pin "8") (pinfunction "8_8") (pintype "bidirectional"))
      (node (ref "J2") (pin "MP1") (pinfunction "MP1_MP1") (pintype "bidirectional"))
      (node (ref "J2") (pin "MP2") (pinfunction "MP2_MP2") (pintype "bidirectional"))
      (node (ref "J3") (pin "A12_B1") (pinfunction "GND_A12_B1") (pintype "power_in"))
      (node (ref "J3") (pin "A1_B12") (pinfunction "GND_A1_B12") (pintype "power_in"))
      (node (ref "J3") (pin "SH1") (pinfunction "SHIELD_SH1") (pintype "passive"))
      (node (ref "J3") (pin "SH2") (pinfunction "SHIELD_SH2") (pintype "passive"))
      (node (ref "J3") (pin "SH3") (pinfunction "SHIELD_SH3") (pintype "passive"))
      (node (ref "J3") (pin "SH4") (pinfunction "SHIELD_SH4") (pintype "passive"))
      (node (ref "R1_USB") (pin "1") (pinfunction "1_1") (pintype "bidirectional"))
      (node (ref "R2_EP_DR") (pin "1") (pinfunction "1_1") (pintype "bidirectional"))
      (node (ref "R2_USB") (pin "2") (pinfunction "2_2") (pintype "bidirectional"))
      (node (ref "R3") (pin "1") (pinfunction "1_1") (pintype "bidirectional"))
      (node (ref "R9") (pin "1") (pinfunction "1_1") (pintype "bidirectional"))
      (node (ref "R_TYPE_SEL") (pin "1") (pinfunction "1_1") (pintype "bidirectional"))
      (node (ref "SJ1") (pin "1") (pinfunction "1_1") (pintype "passive"))
      (node (ref "SW_DN") (pin "1") (pinfunction "1_1") (pintype "passive"))
      (node (ref "SW_ENT") (pin "1") (pinfunction "1_1") (pintype "passive"))
      (node (ref "SW_UP") (pin "1") (pinfunction "1_1") (pintype "passive"))
      (node (ref "TP_BAT_GND") (pin "TP") (pinfunction "TP_TP") (pintype "input"))
      (node (ref "U3") (pin "1") (pinfunction "CTG_1") (pintype "power_in"))
      (node (ref "U3") (pin "4") (pinfunction "GND_4") (pintype "power_in"))
      (node (ref "U3") (pin "6") (pinfunction "QSTRT_6") (pintype "input"))
      (node (ref "U3") (pin "9") (pinfunction "EP_9") (pintype "power_in"))
      (node (ref "U4") (pin "P$74") (pinfunction "VSS_PAD_P$74") (pintype "bidirectional"))
      (node (ref "U4") (pin "P$75") (pinfunction "VSS_PAD_P$75") (pintype "bidirectional"))
      (node (ref "U4") (pin "P$76") (pinfunction "VSS_PAD_P$76") (pintype "bidirectional"))
      (node (ref "U4") (pin "P$77") (pinfunction "VSS_PAD_P$77") (pintype "bidirectional"))
      (node (ref "U4") (pin "P$78") (pinfunction "VSS_PAD_P$78") (pintype "bidirectional"))
      (node (ref "U4") (pin "P$79") (pinfunction "VSS_PAD_P$79") (pintype "bidirectional"))
      (node (ref "U4") (pin "P$80") (pinfunction "VSS_PAD_P$80") (pintype "bidirectional"))
      (node (ref "U4") (pin "P$81") (pinfunction "VSS_PAD_P$81") (pintype "bidirectional"))
      (node (ref "U4") (pin "P$82") (pinfunction "VSS_PAD_P$82") (pintype "bidirectional"))
      (node (ref "U4") (pin "P$83") (pinfunction "VSS_PAD_P$83") (pintype "bidirectional"))
      (node (ref "U4") (pin "P$84") (pinfunction "VSS_PAD_P$84") (pintype "bidirectional"))
      (node (ref "U4") (pin "P$85") (pinfunction "VSS_PAD_P$85") (pintype "bidirectional"))
      (node (ref "U4") (pin "P$86") (pinfunction "VSS_PAD_P$86") (pintype "bidirectional"))
      (node (ref "U4") (pin "P$87") (pinfunction "VSS_PAD_P$87") (pintype "bidirectional"))
      (node (ref "U4") (pin "P$88") (pinfunction "VSS_PAD_P$88") (pintype "bidirectional"))
      (node (ref "U4") (pin "P$89") (pinfunction "VSS_PAD_P$89") (pintype "bidirectional"))
      (node (ref "U4") (pin "P$90") (pinfunction "VSS_PAD_P$90") (pintype "bidirectional"))
      (node (ref "U4") (pin "P$B7") (pinfunction "VSS_P$B7") (pintype "power_in"))
      (node (ref "U4") (pin "P$F23") (pinfunction "VSS_PA_P$F23") (pintype "bidirectional"))
      (node (ref "X1") (pin "2") (pinfunction "2_2") (pintype "passive"))
      (node (ref "X1") (pin "4") (pinfunction "4_4") (pintype "passive"))
    )
    (net (code "17") (name "HAPTIC_EN") (class "Default")
      (node (ref "IC2") (pin "A1") (pinfunction "EN_A1") (pintype "bidirectional"))
      (node (ref "U4") (pin "P$U1") (pinfunction "P0.12_P$U1") (pintype "bidirectional"))
    )
    (net (code "18") (name "IMU_INT1") (class "Default")
      (node (ref "IC3") (pin "5") (pinfunction "INT1_5") (pintype "bidirectional"))
      (node (ref "U4") (pin "P$N1") (pinfunction "P0.08_P$N1") (pintype "bidirectional"))
    )
    (net (code "19") (name "IMU_INT2") (class "Default")
      (node (ref "IC3") (pin "6") (pinfunction "INT2_6") (pintype "bidirectional"))
      (node (ref "U4") (pin "P$P2") (pinfunction "P1.08_P$P2") (pintype "bidirectional"))
    )
    (net (code "20") (name "LX1") (class "Default")
      (node (ref "IC9") (pin "B2") (pinfunction "SW1_1_B2") (pintype "bidirectional"))
      (node (ref "IC9") (pin "B3") (pinfunction "SW1_2_B3") (pintype "bidirectional"))
      (node (ref "L7") (pin "1") (pinfunction "1_1") (pintype "bidirectional"))
    )
    (net (code "21") (name "LX2") (class "Default")
      (node (ref "IC9") (pin "D2") (pinfunction "SW2_1_D2") (pintype "bidirectional"))
      (node (ref "IC9") (pin "D3") (pinfunction "SW2_2_D3") (pintype "bidirectional"))
      (node (ref "L7") (pin "2") (pinfunction "2_2") (pintype "bidirectional"))
    )
    (net (code "22") (name "MOSI") (class "Default")
      (node (ref "J2") (pin "14") (pinfunction "14_14") (pintype "bidirectional"))
      (node (ref "U4") (pin "P$B13") (pinfunction "P0.03/AIN1_P$B13") (pintype "bidirectional"))
    )
    (net (code "23") (name "Net-(ANT1-FEED)") (class "Default")
      (node (ref "ANT1") (pin "1") (pinfunction "FEED_1") (pintype "input"))
      (node (ref "C22") (pin "1") (pinfunction "1_1") (pintype "passive"))
      (node (ref "C4") (pin "1") (pinfunction "1_1") (pintype "passive"))
      (node (ref "L$1") (pin "2") (pinfunction "2_2") (pintype "passive"))
    )
    (net (code "24") (name "Net-(D2-A)") (class "Default")
      (node (ref "C2-EP-DR") (pin "1") (pinfunction "1_1") (pintype "passive"))
      (node (ref "D2") (pin "2") (pinfunction "A_2") (pintype "bidirectional"))
      (node (ref "D4") (pin "1") (pinfunction "K_1") (pintype "bidirectional"))
    )
    (net (code "25") (name "Net-(D5-A)") (class "Default")
      (node (ref "C2-EP-DR") (pin "2") (pinfunction "2_2") (pintype "passive"))
      (node (ref "D5") (pin "2") (pinfunction "A_2") (pintype "bidirectional"))
      (node (ref "L1") (pin "1") (pinfunction "1_1") (pintype "passive"))
      (node (ref "Q3") (pin "3") (pinfunction "D_3") (pintype "bidirectional"))
    )
    (net (code "26") (name "Net-(EPD_C1-Pad2)") (class "Default")
      (node (ref "EPD_C1") (pin "2") (pinfunction "2_2") (pintype "passive"))
      (node (ref "J2") (pin "5") (pinfunction "5_5") (pintype "bidirectional"))
    )
    (net (code "27") (name "Net-(EPD_C2-Pad2)") (class "Default")
      (node (ref "EPD_C2") (pin "2") (pinfunction "2_2") (pintype "passive"))
      (node (ref "J2") (pin "4") (pinfunction "4_4") (pintype "bidirectional"))
    )
    (net (code "28") (name "Net-(EPD_C6-Pad2)") (class "Default")
      (node (ref "EPD_C6") (pin "2") (pinfunction "2_2") (pintype "passive"))
      (node (ref "J2") (pin "18") (pinfunction "18_18") (pintype "bidirectional"))
    )
    (net (code "29") (name "Net-(EPD_C7-Pad2)") (class "Default")
      (node (ref "EPD_C7") (pin "2") (pinfunction "2_2") (pintype "passive"))
      (node (ref "J2") (pin "19") (pinfunction "19_19") (pintype "bidirectional"))
    )
    (net (code "30") (name "Net-(EPD_C8-Pad2)") (class "Default")
      (node (ref "EPD_C8") (pin "2") (pinfunction "2_2") (pintype "passive"))
      (node (ref "J2") (pin "20") (pinfunction "20_20") (pintype "bidirectional"))
    )
    (net (code "31") (name "Net-(EPD_C10-Pad2)") (class "Default")
      (node (ref "EPD_C10") (pin "2") (pinfunction "2_2") (pintype "passive"))
      (node (ref "J2") (pin "22") (pinfunction "22_22") (pintype "bidirectional"))
    )
    (net (code "32") (name "Net-(EPD_C12-Pad2)") (class "Default")
      (node (ref "EPD_C12") (pin "2") (pinfunction "2_2") (pintype "passive"))
      (node (ref "J2") (pin "24") (pinfunction "24_24") (pintype "bidirectional"))
    )
    (net (code "33") (name "Net-(IC1-TS{slash}MR)") (class "Default")
      (node (ref "IC1") (pin "D1") (pinfunction "TS/MR_D1") (pintype "bidirectional"))
      (node (ref "R9") (pin "2") (pinfunction "2_2") (pintype "bidirectional"))
    )
    (net (code "34") (name "Net-(IC2-REG)") (class "Default")
      (node (ref "C32") (pin "2") (pinfunction "2_2") (pintype "passive"))
      (node (ref "IC2") (pin "A2") (pinfunction "REG_A2") (pintype "bidirectional"))
    )
    (net (code "35") (name "Net-(IC3-SDO)") (class "Default")
      (node (ref "IC3") (pin "1") (pinfunction "SDO_1") (pintype "bidirectional"))
      (node (ref "R3") (pin "2") (pinfunction "2_2") (pintype "bidirectional"))
    )
    (net (code "36") (name "Net-(IC9-SCL)") (class "Default")
      (node (ref "IC9") (pin "D1") (pinfunction "SCL_D1") (pintype "bidirectional"))
      (node (ref "R4") (pin "2") (pinfunction "2_2") (pintype "bidirectional"))
    )
    (net (code "37") (name "Net-(IC9-SDA)") (class "Default")
      (node (ref "IC9") (pin "E1") (pinfunction "SDA_E1") (pintype "bidirectional"))
      (node (ref "R2") (pin "2") (pinfunction "2_2") (pintype "bidirectional"))
    )
    (net (code "38") (name "Net-(J3-CC1)") (class "Default")
      (node (ref "J3") (pin "A5") (pinfunction "CC1_A5") (pintype "bidirectional"))
      (node (ref "R1_USB") (pin "2") (pinfunction "2_2") (pintype "bidirectional"))
    )
    (net (code "39") (name "Net-(J3-CC2)") (class "Default")
      (node (ref "J3") (pin "B5") (pinfunction "CC2_B5") (pintype "bidirectional"))
      (node (ref "R2_USB") (pin "1") (pinfunction "1_1") (pintype "bidirectional"))
    )
    (net (code "40") (name "Net-(L2-Pad2)") (class "Default")
      (node (ref "L2") (pin "2") (pinfunction "2_2") (pintype "passive"))
      (node (ref "L3") (pin "1") (pinfunction "1_1") (pintype "passive"))
    )
    (net (code "41") (name "Net-(R1_EP_DR'-Pad1)") (class "Default")
      (node (ref "R1_EP_DR'") (pin "1") (pinfunction "1_1") (pintype "bidirectional"))
      (node (ref "R_TYPE_SEL") (pin "2") (pinfunction "2_2") (pintype "bidirectional"))
      (node (ref "SJ1") (pin "2") (pinfunction "2_2") (pintype "passive"))
    )
    (net (code "42") (name "Net-(U4-ANT)") (class "Default")
      (node (ref "C3") (pin "1") (pinfunction "1_1") (pintype "passive"))
      (node (ref "L$1") (pin "1") (pinfunction "1_1") (pintype "passive"))
      (node (ref "U4") (pin "P$H23") (pinfunction "ANT_P$H23") (pintype "bidirectional"))
    )
    (net (code "43") (name "Net-(U4-DCC)") (class "Default")
      (node (ref "L2") (pin "1") (pinfunction "1_1") (pintype "passive"))
      (node (ref "U4") (pin "P$B3") (pinfunction "DCC_P$B3") (pintype "output"))
    )
    (net (code "44") (name "Net-(U4-DEC1)") (class "Default")
      (node (ref "C5") (pin "1") (pinfunction "1_1") (pintype "passive"))
      (node (ref "U4") (pin "P$C1") (pinfunction "DEC1_P$C1") (pintype "power_in"))
    )
    (net (code "45") (name "Net-(U4-DEC2)") (class "Default")
      (node (ref "C13") (pin "1") (pinfunction "1_1") (pintype "passive"))
      (node (ref "U4") (pin "P$A18") (pinfunction "DEC2_P$A18") (pintype "bidirectional"))
    )
    (net (code "46") (name "Net-(U4-DEC3)") (class "Default")
      (node (ref "C11") (pin "1") (pinfunction "1_1") (pintype "passive"))
      (node (ref "U4") (pin "P$D23") (pinfunction "DEC3_P$D23") (pintype "bidirectional"))
    )
    (net (code "47") (name "Net-(U4-DEC3V3)") (class "Default")
      (node (ref "C20") (pin "1") (pinfunction "1_1") (pintype "passive"))
      (node (ref "U4") (pin "P$AC5") (pinfunction "DEC3V3_P$AC5") (pintype "bidirectional"))
    )
    (net (code "48") (name "Net-(U4-DEC4)") (class "Default")
      (node (ref "C10") (pin "1") (pinfunction "1_1") (pintype "passive"))
      (node (ref "C15") (pin "1") (pinfunction "1_1") (pintype "passive"))
      (node (ref "C16") (pin "1") (pinfunction "1_1") (pintype "passive"))
      (node (ref "L3") (pin "2") (pinfunction "2_2") (pintype "passive"))
      (node (ref "U4") (pin "P$B5") (pinfunction "DEC4_P$B5") (pintype "power_in"))
      (node (ref "U4") (pin "P$E24") (pinfunction "DEC6_P$E24") (pintype "bidirectional"))
    )
    (net (code "49") (name "Net-(U4-DEC5)") (class "Default")
      (node (ref "C9") (pin "1") (pinfunction "1_1") (pintype "passive"))
      (node (ref "U4") (pin "P$N24") (pinfunction "DEC5_P$N24") (pintype "bidirectional"))
    )
    (net (code "50") (name "Net-(U4-XC1)") (class "Default")
      (node (ref "C1") (pin "1") (pinfunction "1_1") (pintype "passive"))
      (node (ref "U4") (pin "P$B24") (pinfunction "XC1_P$B24") (pintype "input"))
      (node (ref "X1") (pin "1") (pinfunction "1_1") (pintype "passive"))
    )
    (net (code "51") (name "Net-(U4-XC2)") (class "Default")
      (node (ref "C2") (pin "1") (pinfunction "1_1") (pintype "passive"))
      (node (ref "U4") (pin "P$A23") (pinfunction "XC2_P$A23") (pintype "output"))
      (node (ref "X1") (pin "3") (pinfunction "3_3") (pintype "passive"))
    )
    (net (code "52") (name "OUT+") (class "Default")
      (node (ref "IC2") (pin "A3") (pinfunction "OUT+_A3") (pintype "bidirectional"))
      (node (ref "OP") (pin "TP") (pinfunction "TP_TP") (pintype "input"))
    )
    (net (code "53") (name "OUT-") (class "Default")
      (node (ref "IC2") (pin "C3") (pinfunction "OUT-_C3") (pintype "bidirectional"))
      (node (ref "ON") (pin "TP") (pinfunction "TP_TP") (pintype "input"))
    )
    (net (code "54") (name "P0.04") (class "Default")
      (node (ref "U4") (pin "P$J1") (pinfunction "P0.04/AIN2_P$J1") (pintype "bidirectional"))
    )
    (net (code "55") (name "P0.09") (class "Default")
      (node (ref "U4") (pin "P$L24") (pinfunction "P0.09/NFC1_P$L24") (pintype "bidirectional"))
    )
    (net (code "56") (name "P0.13") (class "Default")
      (node (ref "C30") (pin "2") (pinfunction "2_2") (pintype "passive"))
      (node (ref "R5") (pin "1") (pinfunction "1_1") (pintype "bidirectional"))
      (node (ref "SW_UP") (pin "2") (pinfunction "2_2") (pintype "passive"))
      (node (ref "U4") (pin "P$AD8") (pinfunction "P0.13_P$AD8") (pintype "bidirectional"))
    )
    (net (code "57") (name "P0.14") (class "Default")
      (node (ref "C31") (pin "2") (pinfunction "2_2") (pintype "passive"))
      (node (ref "R8") (pin "1") (pinfunction "1_1") (pintype "bidirectional"))
      (node (ref "SW_ENT") (pin "2") (pinfunction "2_2") (pintype "passive"))
      (node (ref "U4") (pin "P$AC9") (pinfunction "P0.14_P$AC9") (pintype "bidirectional"))
    )
    (net (code "58") (name "P0.19") (class "Default")
      (node (ref "U4") (pin "P$AC15") (pinfunction "P0.19_P$AC15") (pintype "bidirectional"))
    )
    (net (code "59") (name "P0.20") (class "Default")
      (node (ref "U4") (pin "P$AD16") (pinfunction "P0.20_P$AD16") (pintype "bidirectional"))
    )
    (net (code "60") (name "P0.21") (class "Default")
      (node (ref "U4") (pin "P$AC17") (pinfunction "P0.21_P$AC17") (pintype "bidirectional"))
    )
    (net (code "61") (name "P0.22") (class "Default")
      (node (ref "U4") (pin "P$AD18") (pinfunction "P0.22_P$AD18") (pintype "bidirectional"))
    )
    (net (code "62") (name "P0.23") (class "Default")
      (node (ref "U4") (pin "P$AC19") (pinfunction "P0.23_P$AC19") (pintype "bidirectional"))
    )
    (net (code "63") (name "P0.24") (class "Default")
      (node (ref "U4") (pin "P$AD20") (pinfunction "P0.24_P$AD20") (pintype "bidirectional"))
    )
    (net (code "64") (name "P0.26") (class "Default")
      (node (ref "U4") (pin "P$G1") (pinfunction "P0.26_P$G1") (pintype "bidirectional"))
    )
    (net (code "65") (name "P0.27") (class "Default")
      (node (ref "U4") (pin "P$H2") (pinfunction "P0.27_P$H2") (pintype "bidirectional"))
    )
    (net (code "66") (name "P0.28") (class "Default")
      (node (ref "U4") (pin "P$B11") (pinfunction "P0.28/AIN4_P$B11") (pintype "bidirectional"))
    )
    (net (code "67") (name "P0.29") (class "Default")
      (node (ref "U4") (pin "P$A10") (pinfunction "P0.29/AIN5_P$A10") (pintype "bidirectional"))
    )
    (net (code "68") (name "P0.30") (class "Default")
      (node (ref "U4") (pin "P$B9") (pinfunction "P0.30/AIN6_P$B9") (pintype "bidirectional"))
    )
    (net (code "69") (name "P0.31") (class "Default")
      (node (ref "U4") (pin "P$A8") (pinfunction "P0.31/AIN7_P$A8") (pintype "bidirectional"))
    )
    (net (code "70") (name "P1.01") (class "Default")
      (node (ref "Q1") (pin "1") (pinfunction "G_1") (pintype "bidirectional"))
      (node (ref "R_PWR_EPD") (pin "1") (pinfunction "1_1") (pintype "bidirectional"))
      (node (ref "U4") (pin "P$Y23") (pinfunction "P1.01_P$Y23") (pintype "bidirectional"))
    )
    (net (code "71") (name "P1.02") (class "Default")
      (node (ref "C29") (pin "2") (pinfunction "2_2") (pintype "passive"))
      (node (ref "R7") (pin "1") (pinfunction "1_1") (pintype "bidirectional"))
      (node (ref "SW_DN") (pin "2") (pinfunction "2_2") (pintype "passive"))
      (node (ref "U4") (pin "P$W24") (pinfunction "P1.02_P$W24") (pintype "bidirectional"))
    )
    (net (code "72") (name "P1.03") (class "Default")
      (node (ref "U4") (pin "P$V23") (pinfunction "P1.03_P$V23") (pintype "bidirectional"))
    )
    (net (code "73") (name "P1.04") (class "Default")
      (node (ref "U4") (pin "P$U24") (pinfunction "P1.04_P$U24") (pintype "bidirectional"))
    )
    (net (code "74") (name "P1.05") (class "Default")
      (node (ref "U4") (pin "P$T23") (pinfunction "P1.05_P$T23") (pintype "bidirectional"))
    )
    (net (code "75") (name "P1.06") (class "Default")
      (node (ref "U4") (pin "P$R24") (pinfunction "P1.06_P$R24") (pintype "bidirectional"))
    )
    (net (code "76") (name "P1.07") (class "Default")
      (node (ref "U4") (pin "P$P23") (pinfunction "P1.07_P$P23") (pintype "bidirectional"))
    )
    (net (code "77") (name "P1.09") (class "Default")
      (node (ref "U4") (pin "P$R1") (pinfunction "P1.09_P$R1") (pintype "bidirectional"))
    )
    (net (code "78") (name "P1.10") (class "Default")
      (node (ref "U4") (pin "P$A20") (pinfunction "P1.10_P$A20") (pintype "bidirectional"))
    )
    (net (code "79") (name "P1.11") (class "Default")
      (node (ref "U4") (pin "P$B19") (pinfunction "P1.11_P$B19") (pintype "bidirectional"))
    )
    (net (code "80") (name "P1.12") (class "Default")
      (node (ref "U4") (pin "P$B17") (pinfunction "P1.12_P$B17") (pintype "bidirectional"))
    )
    (net (code "81") (name "P1.13") (class "Default")
      (node (ref "U4") (pin "P$A16") (pinfunction "P1.13_P$A16") (pintype "bidirectional"))
    )
    (net (code "82") (name "P1.14") (class "Default")
      (node (ref "U4") (pin "P$B15") (pinfunction "P1.14_P$B15") (pintype "bidirectional"))
    )
    (net (code "83") (name "P1.15") (class "Default")
      (node (ref "U4") (pin "P$A14") (pinfunction "P1.15_P$A14") (pintype "bidirectional"))
    )
    (net (code "84") (name "PMIC_INT") (class "Default")
      (node (ref "IC1") (pin "A1") (pinfunction "~{INT}_A1") (pintype "bidirectional"))
      (node (ref "U4") (pin "P$T2") (pinfunction "P0.11_P$T2") (pintype "bidirectional"))
    )
    (net (code "85") (name "PREVGH") (class "Default")
      (node (ref "D5") (pin "1") (pinfunction "K_1") (pintype "bidirectional"))
      (node (ref "EPD_C9") (pin "2") (pinfunction "2_2") (pintype "passive"))
      (node (ref "J2") (pin "21") (pinfunction "21_21") (pintype "bidirectional"))
    )
    (net (code "86") (name "PREVGL") (class "Default")
      (node (ref "D4") (pin "2") (pinfunction "A_2") (pintype "bidirectional"))
      (node (ref "EPD_C11") (pin "2") (pinfunction "2_2") (pintype "passive"))
      (node (ref "J2") (pin "23") (pinfunction "23_23") (pintype "bidirectional"))
    )
    (net (code "87") (name "RESE") (class "Default")
      (node (ref "J2") (pin "3") (pinfunction "3_3") (pintype "bidirectional"))
      (node (ref "Q3") (pin "2") (pinfunction "S_2") (pintype "bidirectional"))
      (node (ref "R1_EP_DR'") (pin "2") (pinfunction "2_2") (pintype "bidirectional"))
    )
    (net (code "88") (name "RESET") (class "Default")
      (node (ref "J1") (pin "6") (pinfunction "6_6") (pintype "bidirectional"))
      (node (ref "RESET") (pin "TP") (pinfunction "TP_TP") (pintype "input"))
      (node (ref "U4") (pin "P$AC13") (pinfunction "P0.18/RESET_P$AC13") (pintype "bidirectional"))
    )
    (net (code "89") (name "SCK") (class "Default")
      (node (ref "J2") (pin "13") (pinfunction "13_13") (pintype "bidirectional"))
      (node (ref "U4") (pin "P$A12") (pinfunction "P0.02/AIN0_P$A12") (pintype "bidirectional"))
    )
    (net (code "90") (name "SCL") (class "Default")
      (node (ref "IC1") (pin "B1") (pinfunction "SCL_B1") (pintype "bidirectional"))
      (node (ref "IC2") (pin "C1") (pinfunction "SCL_C1") (pintype "bidirectional"))
      (node (ref "IC3") (pin "12") (pinfunction "SCX_12") (pintype "bidirectional"))
      (node (ref "R17") (pin "2") (pinfunction "2_2") (pintype "bidirectional"))
      (node (ref "R4") (pin "1") (pinfunction "1_1") (pintype "bidirectional"))
      (node (ref "SCL") (pin "TP") (pinfunction "TP_TP") (pintype "input"))
      (node (ref "U3") (pin "7") (pinfunction "SCL_7") (pintype "input"))
    )
    (net (code "91") (name "SCL{slash}2.4C") (class "Default")
      (node (ref "U4") (pin "P$M2") (pinfunction "P0.07_P$M2") (pintype "bidirectional"))
    )
    (net (code "92") (name "SDA") (class "Default")
      (node (ref "IC1") (pin "C1") (pinfunction "SDA_C1") (pintype "bidirectional"))
      (node (ref "IC2") (pin "B2") (pinfunction "SDA_B2") (pintype "bidirectional"))
      (node (ref "IC3") (pin "2") (pinfunction "SDX_2") (pintype "bidirectional"))
      (node (ref "R18") (pin "2") (pinfunction "2_2") (pintype "bidirectional"))
      (node (ref "R2") (pin "1") (pinfunction "1_1") (pintype "bidirectional"))
      (node (ref "SDA") (pin "TP") (pinfunction "TP_TP") (pintype "input"))
      (node (ref "U3") (pin "8") (pinfunction "SDA_8") (pintype "bidirectional"))
      (node (ref "U4") (pin "P$L1") (pinfunction "P0.06_P$L1") (pintype "bidirectional"))
    )
    (net (code "93") (name "SWDCLK") (class "Default")
      (node (ref "J1") (pin "4") (pinfunction "4_4") (pintype "bidirectional"))
      (node (ref "SWDCLK") (pin "TP") (pinfunction "TP_TP") (pintype "input"))
      (node (ref "U4") (pin "P$AA24") (pinfunction "SWDCLK_P$AA24") (pintype "input"))
    )
    (net (code "94") (name "SWDIO") (class "Default")
      (node (ref "J1") (pin "2") (pinfunction "2_2") (pintype "bidirectional"))
      (node (ref "SWDIO") (pin "TP") (pinfunction "TP_TP") (pintype "input"))
      (node (ref "U4") (pin "P$AC24") (pinfunction "SWDIO_P$AC24") (pintype "bidirectional"))
    )
    (net (code "95") (name "SWO") (class "Default")
      (node (ref "SWO") (pin "TP") (pinfunction "TP_TP") (pintype "input"))
      (node (ref "U4") (pin "P$AD22") (pinfunction "P1.00_P$AD22") (pintype "bidirectional"))
    )
    (net (code "96") (name "VBAT") (class "Default")
      (node (ref "C27") (pin "2") (pinfunction "2_2") (pintype "passive"))
      (node (ref "C37") (pin "2") (pinfunction "2_2") (pintype "passive"))
      (node (ref "IC1") (pin "C2") (pinfunction "BAT_C2") (pintype "bidirectional"))
      (node (ref "U3") (pin "2") (pinfunction "CELL_2") (pintype "power_in"))
      (node (ref "U3") (pin "3") (pinfunction "VDD_3") (pintype "power_in"))
      (node (ref "VBAT") (pin "TP") (pinfunction "TP_TP") (pintype "input"))
    )
    (net (code "97") (name "VBUS") (class "Default")
      (node (ref "C21") (pin "1") (pinfunction "1_1") (pintype "passive"))
      (node (ref "C38") (pin "2") (pinfunction "2_2") (pintype "passive"))
      (node (ref "C42") (pin "1") (pinfunction "1_1") (pintype "passive"))
      (node (ref "C43") (pin "1") (pinfunction "1_1") (pintype "passive"))
      (node (ref "D3") (pin "5") (pinfunction "VBUS_5") (pintype "bidirectional"))
      (node (ref "IC1") (pin "A2") (pinfunction "IN_A2") (pintype "bidirectional"))
      (node (ref "J3") (pin "A4_B9") (pinfunction "VBUS_A4_B9") (pintype "power_in"))
      (node (ref "J3") (pin "A9_B4") (pinfunction "VBUS_A9_B4") (pintype "power_in"))
      (node (ref "U4") (pin "P$AD2") (pinfunction "VBUS_P$AD2") (pintype "power_in"))
    )
    (net (code "98") (name "VREG") (class "Default")
      (node (ref "C23") (pin "2") (pinfunction "2_2") (pintype "passive"))
      (node (ref "C24") (pin "2") (pinfunction "2_2") (pintype "passive"))
      (node (ref "C39") (pin "1") (pinfunction "1_1") (pintype "passive"))
      (node (ref "IC1") (pin "B2") (pinfunction "SYS_B2") (pintype "bidirectional"))
      (node (ref "IC9") (pin "A1") (pinfunction "EN_A1") (pintype "bidirectional"))
      (node (ref "IC9") (pin "A2") (pinfunction "VIN_1_A2") (pintype "bidirectional"))
      (node (ref "IC9") (pin "A3") (pinfunction "VIN_2_A3") (pintype "bidirectional"))
      (node (ref "VREG") (pin "TP") (pinfunction "TP_TP") (pintype "input"))
    )
    (net (code "99") (name "unconnected-(ANT1-NC-Pad2)") (class "Default")
      (node (ref "ANT1") (pin "2") (pinfunction "NC_2") (pintype "no_connect"))
    )
    (net (code "100") (name "unconnected-(IC3-ASCL-Pad11)") (class "Default")
      (node (ref "IC3") (pin "11") (pinfunction "ASCL_11") (pintype "bidirectional"))
    )
    (net (code "101") (name "unconnected-(IC3-ASDA-Pad4)") (class "Default")
      (node (ref "IC3") (pin "4") (pinfunction "ASDA_4") (pintype "bidirectional"))
    )
    (net (code "102") (name "unconnected-(J2-Pad1)") (class "Default")
      (node (ref "J2") (pin "1") (pinfunction "1_1") (pintype "bidirectional"))
    )
    (net (code "103") (name "unconnected-(J2-Pad6)") (class "Default")
      (node (ref "J2") (pin "6") (pinfunction "6_6") (pintype "bidirectional"))
    )
    (net (code "104") (name "unconnected-(J2-Pad7)") (class "Default")
      (node (ref "J2") (pin "7") (pinfunction "7_7") (pintype "bidirectional"))
    )
    (net (code "105") (name "unconnected-(J3-SBU1-PadA8)") (class "Default")
      (node (ref "J3") (pin "A8") (pinfunction "SBU1_A8") (pintype "bidirectional"))
    )
    (net (code "106") (name "unconnected-(J3-SBU2-PadB8)") (class "Default")
      (node (ref "J3") (pin "B8") (pinfunction "SBU2_B8") (pintype "bidirectional"))
    )
    (net (code "107") (name "unconnected-(U4-DCCH-PadP$AB2)") (class "Default")
      (node (ref "U4") (pin "P$AB2") (pinfunction "DCCH_P$AB2") (pintype "bidirectional"))
    )
  )
)
